# SMRT_CLK.net
KiCad netlist of a schematic drawn in EAGLE
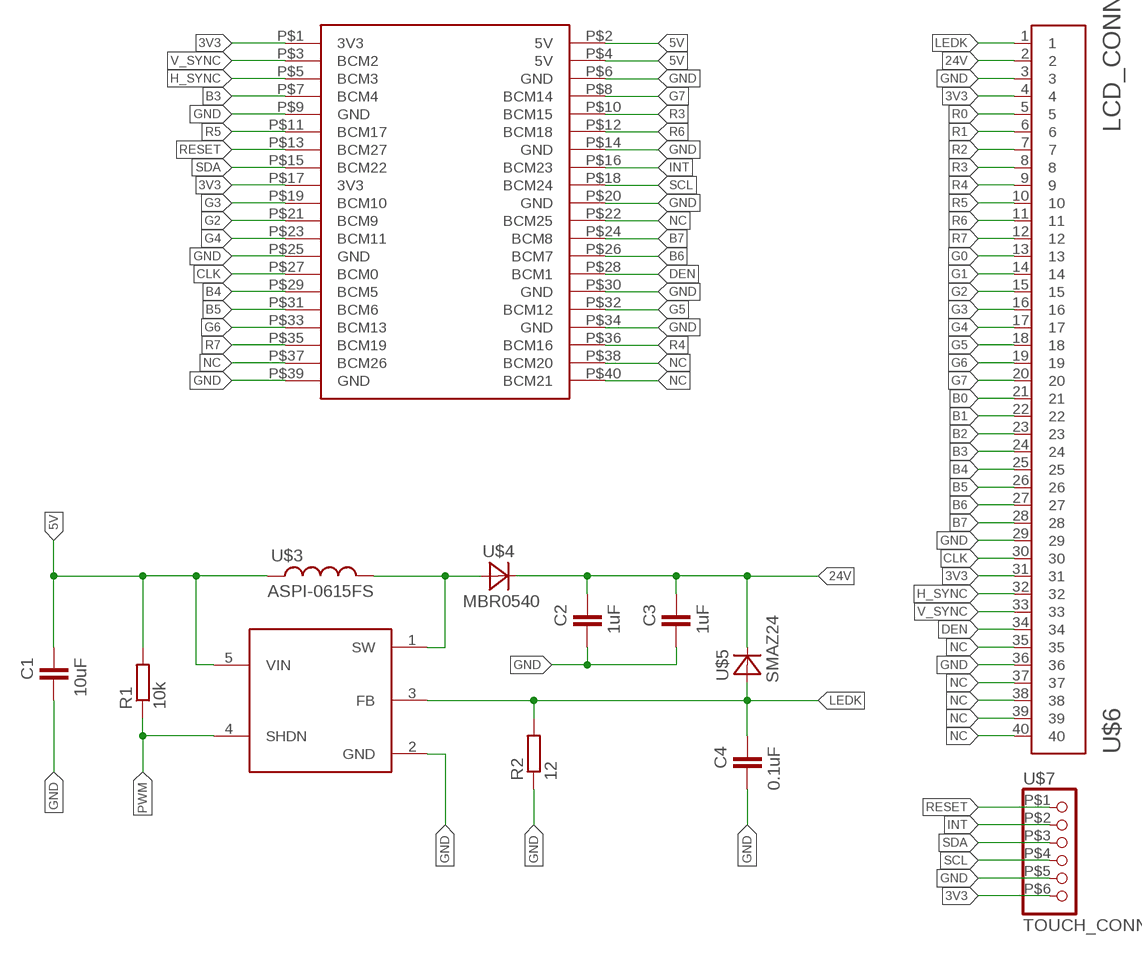
[diagram p0: schematic, sheet 1]

(export (version "E")
  (design (tool "Eeschema 10.0.6"))
  (components
    (comp (ref "C1")
      (value "10uF")
      (footprint "eagle-import:C0805")
      (libsource (lib "eagle-import") (part "C-EUC0805"))
    )
    (comp (ref "C2")
      (value "1uF")
      (footprint "eagle-import:C0805")
      (libsource (lib "eagle-import") (part "C-EUC0805"))
    )
    (comp (ref "C3")
      (value "1uF")
      (footprint "eagle-import:C0805")
      (libsource (lib "eagle-import") (part "C-EUC0805"))
    )
    (comp (ref "C4")
      (value "0.1uF")
      (footprint "eagle-import:C0805")
      (libsource (lib "eagle-import") (part "C-EUC0805"))
    )
    (comp (ref "R1")
      (value "10k")
      (footprint "eagle-import:R0805")
      (libsource (lib "eagle-import") (part "R-EU_R0805"))
    )
    (comp (ref "R2")
      (value "12")
      (footprint "eagle-import:R0805")
      (libsource (lib "eagle-import") (part "R-EU_R0805"))
    )
    (comp (ref "U$1")
      (value "SMRT_CLK")
      (footprint "eagle-import:FULL_BOARD")
      (libsource (lib "eagle-import") (part "SMRT_CLK"))
    )
    (comp (ref "U$2")
      (value "FAN5333BSX")
      (footprint "eagle-import:SOT23-5")
      (libsource (lib "eagle-import") (part "FAN5333BSX"))
    )
    (comp (ref "U$3")
      (value "ASPI-0615FS")
      (footprint "eagle-import:CUST_IND")
      (libsource (lib "eagle-import") (part "ASPI-0615FS"))
    )
    (comp (ref "U$4")
      (value "MBR0540")
      (footprint "eagle-import:SOD-123_MINI-SMA")
      (libsource (lib "eagle-import") (part "MBR0540"))
    )
    (comp (ref "U$5")
      (value "SMAZ24")
      (footprint "eagle-import:DO-214AC")
      (libsource (lib "eagle-import") (part "SMAZ24"))
    )
    (comp (ref "U$6")
      (value "LCD_CONN")
      (footprint "eagle-import:4-1734839-0")
      (libsource (lib "eagle-import") (part "LCD_CONN"))
    )
    (comp (ref "U$7")
      (value "TOUCH_CONN")
      (footprint "eagle-import:052207")
      (libsource (lib "eagle-import") (part "TOUCH_CONN"))
    )
  )
  (nets
    (net (code "1") (name "3V3") (class "Default")
      (node (ref "U$1") (pin "P$1") (pinfunction "3V3_P$1") (pintype "bidirectional"))
      (node (ref "U$1") (pin "P$17") (pinfunction "3V3_P$17") (pintype "bidirectional"))
      (node (ref "U$6") (pin "31") (pinfunction "31_31") (pintype "bidirectional"))
      (node (ref "U$6") (pin "4") (pinfunction "4_4") (pintype "bidirectional"))
      (node (ref "U$7") (pin "P$6") (pinfunction "6_P$6") (pintype "passive"))
    )
    (net (code "2") (name "5V") (class "Default")
      (node (ref "C1") (pin "2") (pinfunction "2_2") (pintype "passive"))
      (node (ref "R1") (pin "2") (pinfunction "2_2") (pintype "passive"))
      (node (ref "U$1") (pin "P$2") (pinfunction "5V_P$2") (pintype "bidirectional"))
      (node (ref "U$1") (pin "P$4") (pinfunction "5V_P$4") (pintype "bidirectional"))
      (node (ref "U$2") (pin "5") (pinfunction "VIN_5") (pintype "bidirectional"))
      (node (ref "U$3") (pin "P$1") (pinfunction "1_P$1") (pintype "passive"))
    )
    (net (code "3") (name "24V") (class "Default")
      (node (ref "C2") (pin "2") (pinfunction "2_2") (pintype "passive"))
      (node (ref "C3") (pin "2") (pinfunction "2_2") (pintype "passive"))
      (node (ref "U$4") (pin "C") (pinfunction "C_C") (pintype "passive"))
      (node (ref "U$5") (pin "C") (pinfunction "C_C") (pintype "passive"))
      (node (ref "U$6") (pin "2") (pinfunction "2_2") (pintype "bidirectional"))
    )
    (net (code "4") (name "B0") (class "Default")
      (node (ref "U$6") (pin "21") (pinfunction "21_21") (pintype "bidirectional"))
    )
    (net (code "5") (name "B1") (class "Default")
      (node (ref "U$6") (pin "22") (pinfunction "22_22") (pintype "bidirectional"))
    )
    (net (code "6") (name "B2") (class "Default")
      (node (ref "U$6") (pin "23") (pinfunction "23_23") (pintype "bidirectional"))
    )
    (net (code "7") (name "B3") (class "Default")
      (node (ref "U$1") (pin "P$7") (pinfunction "BCM4_P$7") (pintype "bidirectional"))
      (node (ref "U$6") (pin "24") (pinfunction "24_24") (pintype "bidirectional"))
    )
    (net (code "8") (name "B4") (class "Default")
      (node (ref "U$1") (pin "P$29") (pinfunction "BCM5_P$29") (pintype "bidirectional"))
      (node (ref "U$6") (pin "25") (pinfunction "25_25") (pintype "bidirectional"))
    )
    (net (code "9") (name "B5") (class "Default")
      (node (ref "U$1") (pin "P$31") (pinfunction "BCM6_P$31") (pintype "bidirectional"))
      (node (ref "U$6") (pin "26") (pinfunction "26_26") (pintype "bidirectional"))
    )
    (net (code "10") (name "B6") (class "Default")
      (node (ref "U$1") (pin "P$26") (pinfunction "BCM7_P$26") (pintype "bidirectional"))
      (node (ref "U$6") (pin "27") (pinfunction "27_27") (pintype "bidirectional"))
    )
    (net (code "11") (name "B7") (class "Default")
      (node (ref "U$1") (pin "P$24") (pinfunction "BCM8_P$24") (pintype "bidirectional"))
      (node (ref "U$6") (pin "28") (pinfunction "28_28") (pintype "bidirectional"))
    )
    (net (code "12") (name "CLK") (class "Default")
      (node (ref "U$1") (pin "P$27") (pinfunction "BCM0_P$27") (pintype "bidirectional"))
      (node (ref "U$6") (pin "30") (pinfunction "30_30") (pintype "bidirectional"))
    )
    (net (code "13") (name "DEN") (class "Default")
      (node (ref "U$1") (pin "P$28") (pinfunction "BCM1_P$28") (pintype "bidirectional"))
      (node (ref "U$6") (pin "34") (pinfunction "34_34") (pintype "bidirectional"))
    )
    (net (code "14") (name "G0") (class "Default")
      (node (ref "U$6") (pin "13") (pinfunction "13_13") (pintype "bidirectional"))
    )
    (net (code "15") (name "G1") (class "Default")
      (node (ref "U$6") (pin "14") (pinfunction "14_14") (pintype "bidirectional"))
    )
    (net (code "16") (name "G2") (class "Default")
      (node (ref "U$1") (pin "P$21") (pinfunction "BCM9_P$21") (pintype "bidirectional"))
      (node (ref "U$6") (pin "15") (pinfunction "15_15") (pintype "bidirectional"))
    )
    (net (code "17") (name "G3") (class "Default")
      (node (ref "U$1") (pin "P$19") (pinfunction "BCM10_P$19") (pintype "bidirectional"))
      (node (ref "U$6") (pin "16") (pinfunction "16_16") (pintype "bidirectional"))
    )
    (net (code "18") (name "G4") (class "Default")
      (node (ref "U$1") (pin "P$23") (pinfunction "BCM11_P$23") (pintype "bidirectional"))
      (node (ref "U$6") (pin "17") (pinfunction "17_17") (pintype "bidirectional"))
    )
    (net (code "19") (name "G5") (class "Default")
      (node (ref "U$1") (pin "P$32") (pinfunction "BCM12_P$32") (pintype "bidirectional"))
      (node (ref "U$6") (pin "18") (pinfunction "18_18") (pintype "bidirectional"))
    )
    (net (code "20") (name "G6") (class "Default")
      (node (ref "U$1") (pin "P$33") (pinfunction "BCM13_P$33") (pintype "bidirectional"))
      (node (ref "U$6") (pin "19") (pinfunction "19_19") (pintype "bidirectional"))
    )
    (net (code "21") (name "G7") (class "Default")
      (node (ref "U$1") (pin "P$8") (pinfunction "BCM14_P$8") (pintype "bidirectional"))
      (node (ref "U$6") (pin "20") (pinfunction "20_20") (pintype "bidirectional"))
    )
    (net (code "22") (name "GND") (class "Default")
      (node (ref "C1") (pin "1") (pinfunction "1_1") (pintype "passive"))
      (node (ref "C2") (pin "1") (pinfunction "1_1") (pintype "passive"))
      (node (ref "C3") (pin "1") (pinfunction "1_1") (pintype "passive"))
      (node (ref "C4") (pin "1") (pinfunction "1_1") (pintype "passive"))
      (node (ref "R2") (pin "1") (pinfunction "1_1") (pintype "passive"))
      (node (ref "U$1") (pin "P$14") (pinfunction "GND_P$14") (pintype "bidirectional"))
      (node (ref "U$1") (pin "P$20") (pinfunction "GND_P$20") (pintype "bidirectional"))
      (node (ref "U$1") (pin "P$25") (pinfunction "GND_P$25") (pintype "bidirectional"))
      (node (ref "U$1") (pin "P$30") (pinfunction "GND_P$30") (pintype "bidirectional"))
      (node (ref "U$1") (pin "P$34") (pinfunction "GND_P$34") (pintype "bidirectional"))
      (node (ref "U$1") (pin "P$39") (pinfunction "GND_P$39") (pintype "bidirectional"))
      (node (ref "U$1") (pin "P$6") (pinfunction "GND_P$6") (pintype "bidirectional"))
      (node (ref "U$1") (pin "P$9") (pinfunction "GND_P$9") (pintype "bidirectional"))
      (node (ref "U$2") (pin "2") (pinfunction "GND_2") (pintype "bidirectional"))
      (node (ref "U$6") (pin "29") (pinfunction "29_29") (pintype "bidirectional"))
      (node (ref "U$6") (pin "3") (pinfunction "3_3") (pintype "bidirectional"))
      (node (ref "U$6") (pin "36") (pinfunction "36_36") (pintype "bidirectional"))
      (node (ref "U$7") (pin "P$5") (pinfunction "5_P$5") (pintype "passive"))
    )
    (net (code "23") (name "H_SYNC") (class "Default")
      (node (ref "U$1") (pin "P$5") (pinfunction "BCM3_P$5") (pintype "bidirectional"))
      (node (ref "U$6") (pin "32") (pinfunction "32_32") (pintype "bidirectional"))
    )
    (net (code "24") (name "INT") (class "Default")
      (node (ref "U$1") (pin "P$16") (pinfunction "BCM23_P$16") (pintype "bidirectional"))
      (node (ref "U$7") (pin "P$2") (pinfunction "2_P$2") (pintype "passive"))
    )
    (net (code "25") (name "LEDK") (class "Default")
      (node (ref "C4") (pin "2") (pinfunction "2_2") (pintype "passive"))
      (node (ref "R2") (pin "2") (pinfunction "2_2") (pintype "passive"))
      (node (ref "U$2") (pin "3") (pinfunction "FB_3") (pintype "bidirectional"))
      (node (ref "U$5") (pin "A") (pinfunction "A_A") (pintype "passive"))
      (node (ref "U$6") (pin "1") (pinfunction "1_1") (pintype "bidirectional"))
    )
    (net (code "26") (name "NC") (class "Default")
      (node (ref "U$1") (pin "P$22") (pinfunction "BCM25_P$22") (pintype "bidirectional"))
      (node (ref "U$1") (pin "P$37") (pinfunction "BCM26_P$37") (pintype "bidirectional"))
      (node (ref "U$1") (pin "P$38") (pinfunction "BCM20_P$38") (pintype "bidirectional"))
      (node (ref "U$1") (pin "P$40") (pinfunction "BCM21_P$40") (pintype "bidirectional"))
      (node (ref "U$6") (pin "35") (pinfunction "35_35") (pintype "bidirectional"))
      (node (ref "U$6") (pin "37") (pinfunction "37_37") (pintype "bidirectional"))
      (node (ref "U$6") (pin "38") (pinfunction "38_38") (pintype "bidirectional"))
      (node (ref "U$6") (pin "39") (pinfunction "39_39") (pintype "bidirectional"))
      (node (ref "U$6") (pin "40") (pinfunction "40_40") (pintype "bidirectional"))
    )
    (net (code "27") (name "Net-(U$2-SW)") (class "Default")
      (node (ref "U$2") (pin "1") (pinfunction "SW_1") (pintype "bidirectional"))
      (node (ref "U$3") (pin "P$2") (pinfunction "2_P$2") (pintype "passive"))
      (node (ref "U$4") (pin "A") (pinfunction "A_A") (pintype "passive"))
    )
    (net (code "28") (name "PWM") (class "Default")
      (node (ref "R1") (pin "1") (pinfunction "1_1") (pintype "passive"))
      (node (ref "U$2") (pin "4") (pinfunction "SHDN_4") (pintype "bidirectional"))
    )
    (net (code "29") (name "R0") (class "Default")
      (node (ref "U$6") (pin "5") (pinfunction "5_5") (pintype "bidirectional"))
    )
    (net (code "30") (name "R1") (class "Default")
      (node (ref "U$6") (pin "6") (pinfunction "6_6") (pintype "bidirectional"))
    )
    (net (code "31") (name "R2") (class "Default")
      (node (ref "U$6") (pin "7") (pinfunction "7_7") (pintype "bidirectional"))
    )
    (net (code "32") (name "R3") (class "Default")
      (node (ref "U$1") (pin "P$10") (pinfunction "BCM15_P$10") (pintype "bidirectional"))
      (node (ref "U$6") (pin "8") (pinfunction "8_8") (pintype "bidirectional"))
    )
    (net (code "33") (name "R4") (class "Default")
      (node (ref "U$1") (pin "P$36") (pinfunction "BCM16_P$36") (pintype "bidirectional"))
      (node (ref "U$6") (pin "9") (pinfunction "9_9") (pintype "bidirectional"))
    )
    (net (code "34") (name "R5") (class "Default")
      (node (ref "U$1") (pin "P$11") (pinfunction "BCM17_P$11") (pintype "bidirectional"))
      (node (ref "U$6") (pin "10") (pinfunction "10_10") (pintype "bidirectional"))
    )
    (net (code "35") (name "R6") (class "Default")
      (node (ref "U$1") (pin "P$12") (pinfunction "BCM18_P$12") (pintype "bidirectional"))
      (node (ref "U$6") (pin "11") (pinfunction "11_11") (pintype "bidirectional"))
    )
    (net (code "36") (name "R7") (class "Default")
      (node (ref "U$1") (pin "P$35") (pinfunction "BCM19_P$35") (pintype "bidirectional"))
      (node (ref "U$6") (pin "12") (pinfunction "12_12") (pintype "bidirectional"))
    )
    (net (code "37") (name "RESET") (class "Default")
      (node (ref "U$1") (pin "P$13") (pinfunction "BCM27_P$13") (pintype "bidirectional"))
      (node (ref "U$7") (pin "P$1") (pinfunction "1_P$1") (pintype "passive"))
    )
    (net (code "38") (name "SCL") (class "Default")
      (node (ref "U$1") (pin "P$18") (pinfunction "BCM24_P$18") (pintype "bidirectional"))
      (node (ref "U$7") (pin "P$4") (pinfunction "4_P$4") (pintype "passive"))
    )
    (net (code "39") (name "SDA") (class "Default")
      (node (ref "U$1") (pin "P$15") (pinfunction "BCM22_P$15") (pintype "bidirectional"))
      (node (ref "U$7") (pin "P$3") (pinfunction "3_P$3") (pintype "passive"))
    )
    (net (code "40") (name "V_SYNC") (class "Default")
      (node (ref "U$1") (pin "P$3") (pinfunction "BCM2_P$3") (pintype "bidirectional"))
      (node (ref "U$6") (pin "33") (pinfunction "33_33") (pintype "bidirectional"))
    )
  )
)
